# local_osc.net
KiCad netlist of a schematic drawn in EAGLE
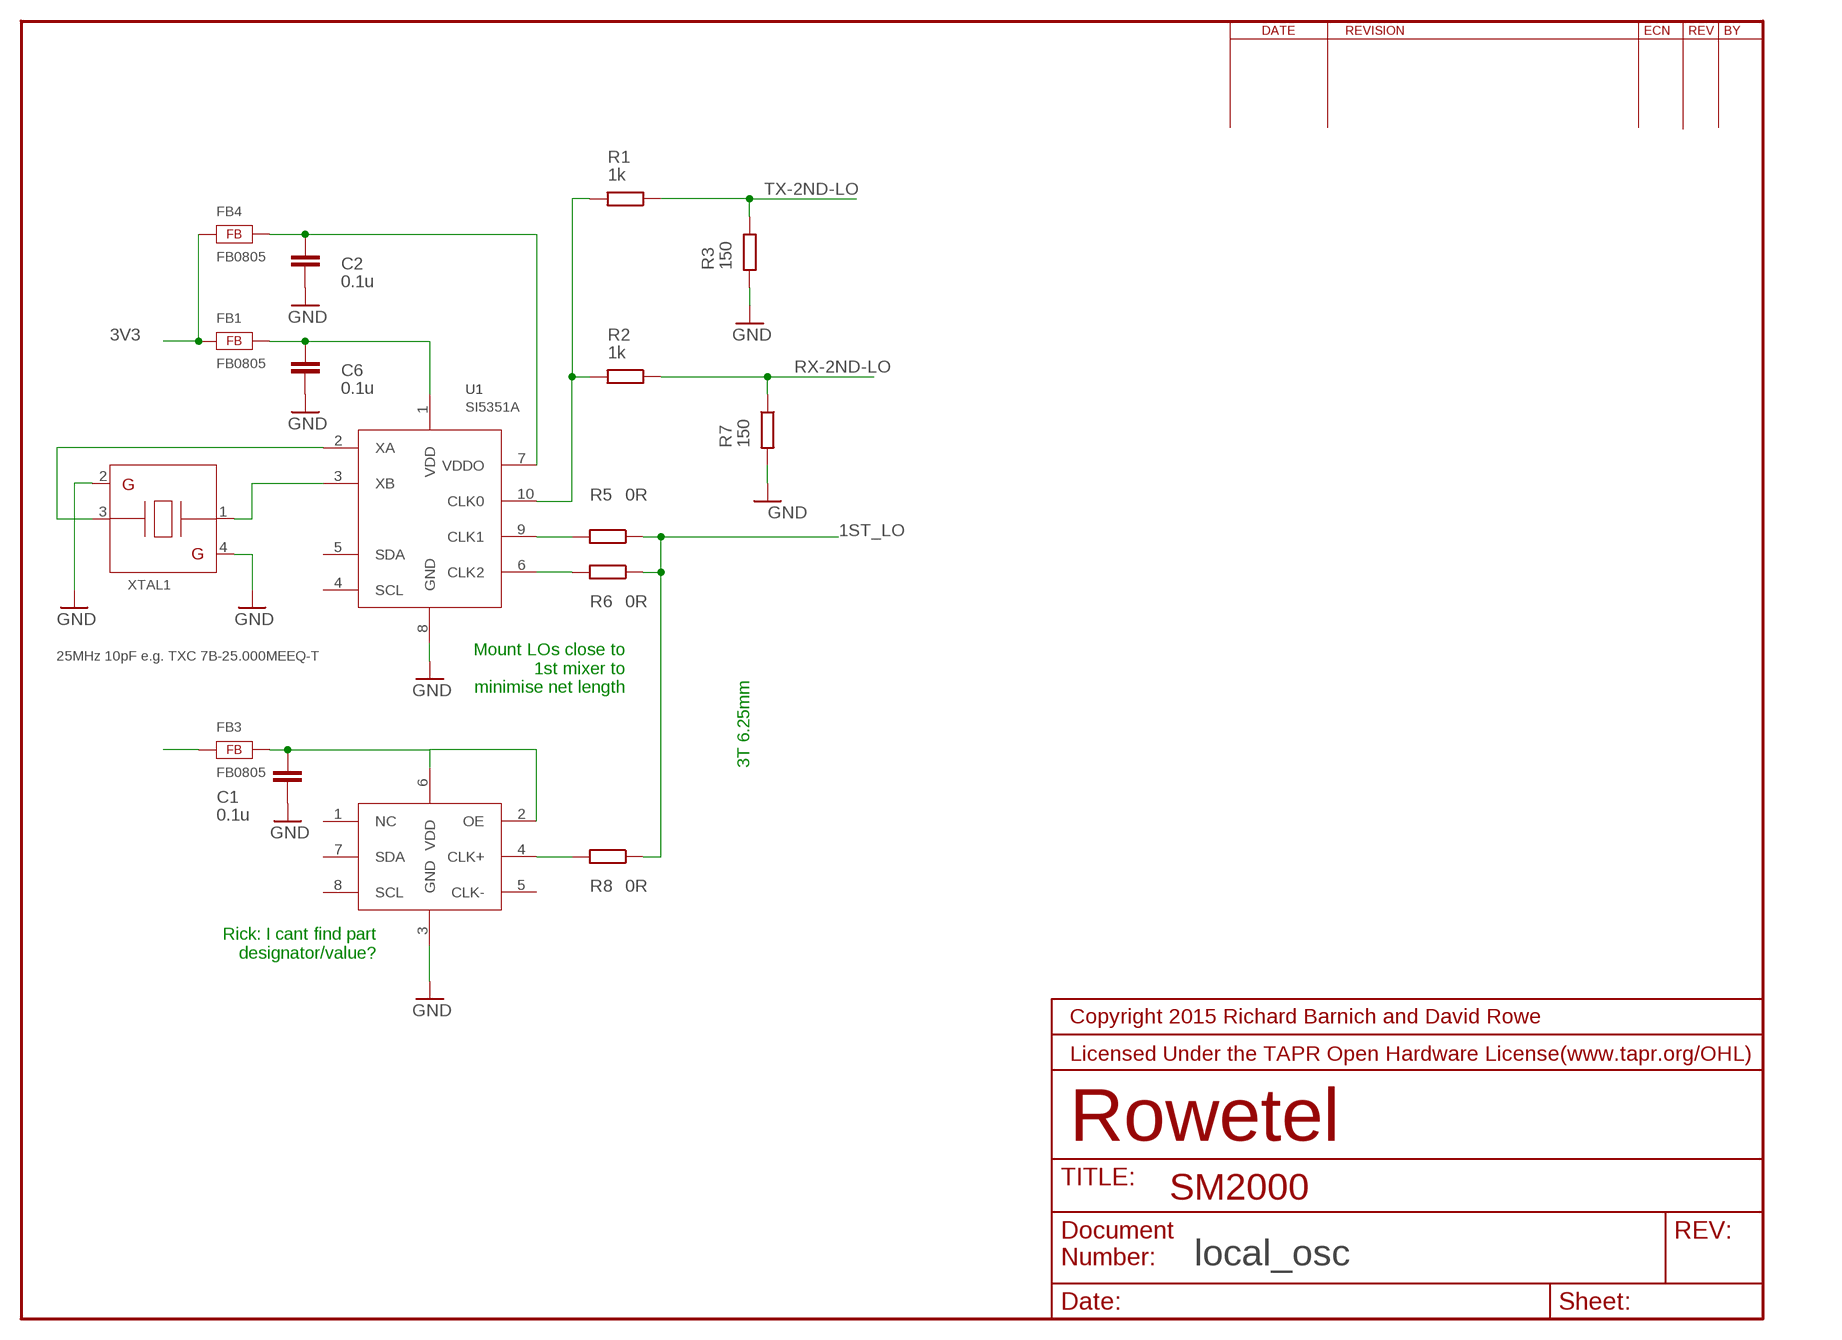
[diagram p0: schematic, sheet 1]

(export (version "E")
  (design (tool "Eeschema 10.0.6"))
  (components
    (comp (ref "C1")
      (value "0.1u")
      (footprint "eagle-import:C025-024X044")
      (libsource (lib "eagle-import") (part "C-EU025-024X044"))
    )
    (comp (ref "C2")
      (value "0.1u")
      (footprint "eagle-import:C025-024X044")
      (libsource (lib "eagle-import") (part "C-EU025-024X044"))
    )
    (comp (ref "C6")
      (value "0.1u")
      (footprint "eagle-import:C025-024X044")
      (libsource (lib "eagle-import") (part "C-EU025-024X044"))
    )
    (comp (ref "FB1")
      (value "FB0805")
      (footprint "eagle-import:FE0805")
      (libsource (lib "eagle-import") (part "FB0805"))
    )
    (comp (ref "FB3")
      (value "FB0805")
      (footprint "eagle-import:FE0805")
      (libsource (lib "eagle-import") (part "FB0805"))
    )
    (comp (ref "FB4")
      (value "FB0805")
      (footprint "eagle-import:FE0805")
      (libsource (lib "eagle-import") (part "FB0805"))
    )
    (comp (ref "R1")
      (value "1k")
      (footprint "eagle-import:RESC2012X70N")
      (libsource (lib "eagle-import") (part "RESISTOR_0805"))
    )
    (comp (ref "R2")
      (value "1k")
      (footprint "eagle-import:RESC2012X70N")
      (libsource (lib "eagle-import") (part "RESISTOR_0805"))
    )
    (comp (ref "R3")
      (value "150")
      (footprint "eagle-import:RESC2012X70N")
      (libsource (lib "eagle-import") (part "RESISTOR_0805"))
    )
    (comp (ref "R5")
      (value "0R")
      (footprint "eagle-import:RESC2012X70N")
      (libsource (lib "eagle-import") (part "RESISTOR_0805"))
    )
    (comp (ref "R6")
      (value "0R")
      (footprint "eagle-import:RESC2012X70N")
      (libsource (lib "eagle-import") (part "RESISTOR_0805"))
    )
    (comp (ref "R7")
      (value "150")
      (footprint "eagle-import:RESC2012X70N")
      (libsource (lib "eagle-import") (part "RESISTOR_0805"))
    )
    (comp (ref "R8")
      (value "0R")
      (footprint "eagle-import:RESC2012X70N")
      (libsource (lib "eagle-import") (part "RESISTOR_0805"))
    )
    (comp (ref "U1")
      (value "SI5351A")
      (footprint "eagle-import:MSOP10")
      (libsource (lib "eagle-import") (part "SI5351A"))
    )
    (comp (ref "U2")
      (value "SI570CAC000141DG")
      (footprint "eagle-import:SI570")
      (libsource (lib "eagle-import") (part "SI570"))
    )
    (comp (ref "XTAL1")
      (value "25MHz 10pF e.g. TXC 7B-25.000MEEQ-T")
      (footprint "eagle-import:XTAL-FY0800035")
      (libsource (lib "eagle-import") (part "XTAL-FY0800035"))
    )
  )
  (nets
    (net (code "1") (name "/1ST_LO") (class "Default")
      (node (ref "R5") (pin "1") (pinfunction "1_1") (pintype "passive"))
      (node (ref "R6") (pin "1") (pinfunction "1_1") (pintype "passive"))
      (node (ref "R8") (pin "1") (pinfunction "1_1") (pintype "passive"))
    )
    (net (code "2") (name "/3V3") (class "Default")
      (node (ref "FB1") (pin "1") (pinfunction "1_1") (pintype "passive"))
      (node (ref "FB4") (pin "1") (pinfunction "1_1") (pintype "passive"))
    )
    (net (code "3") (name "/RX-2ND-LO") (class "Default")
      (node (ref "R2") (pin "1") (pinfunction "1_1") (pintype "passive"))
      (node (ref "R7") (pin "1") (pinfunction "1_1") (pintype "passive"))
    )
    (net (code "4") (name "/TX-2ND-LO") (class "Default")
      (node (ref "R1") (pin "1") (pinfunction "1_1") (pintype "passive"))
      (node (ref "R3") (pin "1") (pinfunction "1_1") (pintype "passive"))
    )
    (net (code "5") (name "GND") (class "Default")
      (node (ref "C1") (pin "2") (pinfunction "2_2") (pintype "passive"))
      (node (ref "C2") (pin "2") (pinfunction "2_2") (pintype "passive"))
      (node (ref "C6") (pin "2") (pinfunction "2_2") (pintype "passive"))
      (node (ref "R3") (pin "2") (pinfunction "2_2") (pintype "passive"))
      (node (ref "R7") (pin "2") (pinfunction "2_2") (pintype "passive"))
      (node (ref "U1") (pin "8") (pinfunction "GND_8") (pintype "power_in"))
      (node (ref "U2") (pin "3") (pinfunction "GND_3") (pintype "power_in"))
      (node (ref "XTAL1") (pin "2") (pinfunction "2_2") (pintype "bidirectional"))
      (node (ref "XTAL1") (pin "4") (pinfunction "4_4") (pintype "bidirectional"))
    )
    (net (code "6") (name "Net-(U1-CLK0)") (class "Default")
      (node (ref "R1") (pin "2") (pinfunction "2_2") (pintype "passive"))
      (node (ref "R2") (pin "2") (pinfunction "2_2") (pintype "passive"))
      (node (ref "U1") (pin "10") (pinfunction "CLK0_10") (pintype "output"))
    )
    (net (code "7") (name "Net-(U1-CLK1)") (class "Default")
      (node (ref "R5") (pin "2") (pinfunction "2_2") (pintype "passive"))
      (node (ref "U1") (pin "9") (pinfunction "CLK1_9") (pintype "output"))
    )
    (net (code "8") (name "Net-(U1-CLK2)") (class "Default")
      (node (ref "R6") (pin "2") (pinfunction "2_2") (pintype "passive"))
      (node (ref "U1") (pin "6") (pinfunction "CLK2_6") (pintype "output"))
    )
    (net (code "9") (name "Net-(U1-VDD)") (class "Default")
      (node (ref "C6") (pin "1") (pinfunction "1_1") (pintype "passive"))
      (node (ref "FB1") (pin "2") (pinfunction "2_2") (pintype "passive"))
      (node (ref "U1") (pin "1") (pinfunction "VDD_1") (pintype "power_in"))
    )
    (net (code "10") (name "Net-(U1-VDDO)") (class "Default")
      (node (ref "C2") (pin "1") (pinfunction "1_1") (pintype "passive"))
      (node (ref "FB4") (pin "2") (pinfunction "2_2") (pintype "passive"))
      (node (ref "U1") (pin "7") (pinfunction "VDDO_7") (pintype "power_in"))
    )
    (net (code "11") (name "Net-(U1-XA)") (class "Default")
      (node (ref "U1") (pin "2") (pinfunction "XA_2") (pintype "bidirectional"))
      (node (ref "XTAL1") (pin "3") (pinfunction "3_3") (pintype "bidirectional"))
    )
    (net (code "12") (name "Net-(U1-XB)") (class "Default")
      (node (ref "U1") (pin "3") (pinfunction "XB_3") (pintype "bidirectional"))
      (node (ref "XTAL1") (pin "1") (pinfunction "1_1") (pintype "bidirectional"))
    )
    (net (code "13") (name "Net-(U2-CLK+)") (class "Default")
      (node (ref "R8") (pin "2") (pinfunction "2_2") (pintype "passive"))
      (node (ref "U2") (pin "4") (pinfunction "CLK+_4") (pintype "output"))
    )
    (net (code "14") (name "Net-(U2-OE)") (class "Default")
      (node (ref "C1") (pin "1") (pinfunction "1_1") (pintype "passive"))
      (node (ref "FB3") (pin "2") (pinfunction "2_2") (pintype "passive"))
      (node (ref "U2") (pin "2") (pinfunction "OE_2") (pintype "input"))
      (node (ref "U2") (pin "6") (pinfunction "VDD_6") (pintype "power_in"))
    )
    (net (code "15") (name "unconnected-(FB3-Pad1)") (class "Default")
      (node (ref "FB3") (pin "1") (pinfunction "1_1") (pintype "passive"))
    )
    (net (code "16") (name "unconnected-(U1-SCL-Pad4)") (class "Default")
      (node (ref "U1") (pin "4") (pinfunction "SCL_4") (pintype "bidirectional"))
    )
    (net (code "17") (name "unconnected-(U1-SDA-Pad5)") (class "Default")
      (node (ref "U1") (pin "5") (pinfunction "SDA_5") (pintype "bidirectional"))
    )
    (net (code "18") (name "unconnected-(U2-CLK--Pad5)") (class "Default")
      (node (ref "U2") (pin "5") (pinfunction "CLK-_5") (pintype "output"))
    )
    (net (code "19") (name "unconnected-(U2-NC-Pad1)") (class "Default")
      (node (ref "U2") (pin "1") (pinfunction "NC_1") (pintype "no_connect"))
    )
    (net (code "20") (name "unconnected-(U2-SCL-Pad8)") (class "Default")
      (node (ref "U2") (pin "8") (pinfunction "SCL_8") (pintype "bidirectional"))
    )
    (net (code "21") (name "unconnected-(U2-SDA-Pad7)") (class "Default")
      (node (ref "U2") (pin "7") (pinfunction "SDA_7") (pintype "bidirectional"))
    )
  )
)
